# pm2019.net
KiCad netlist of a schematic drawn in EAGLE
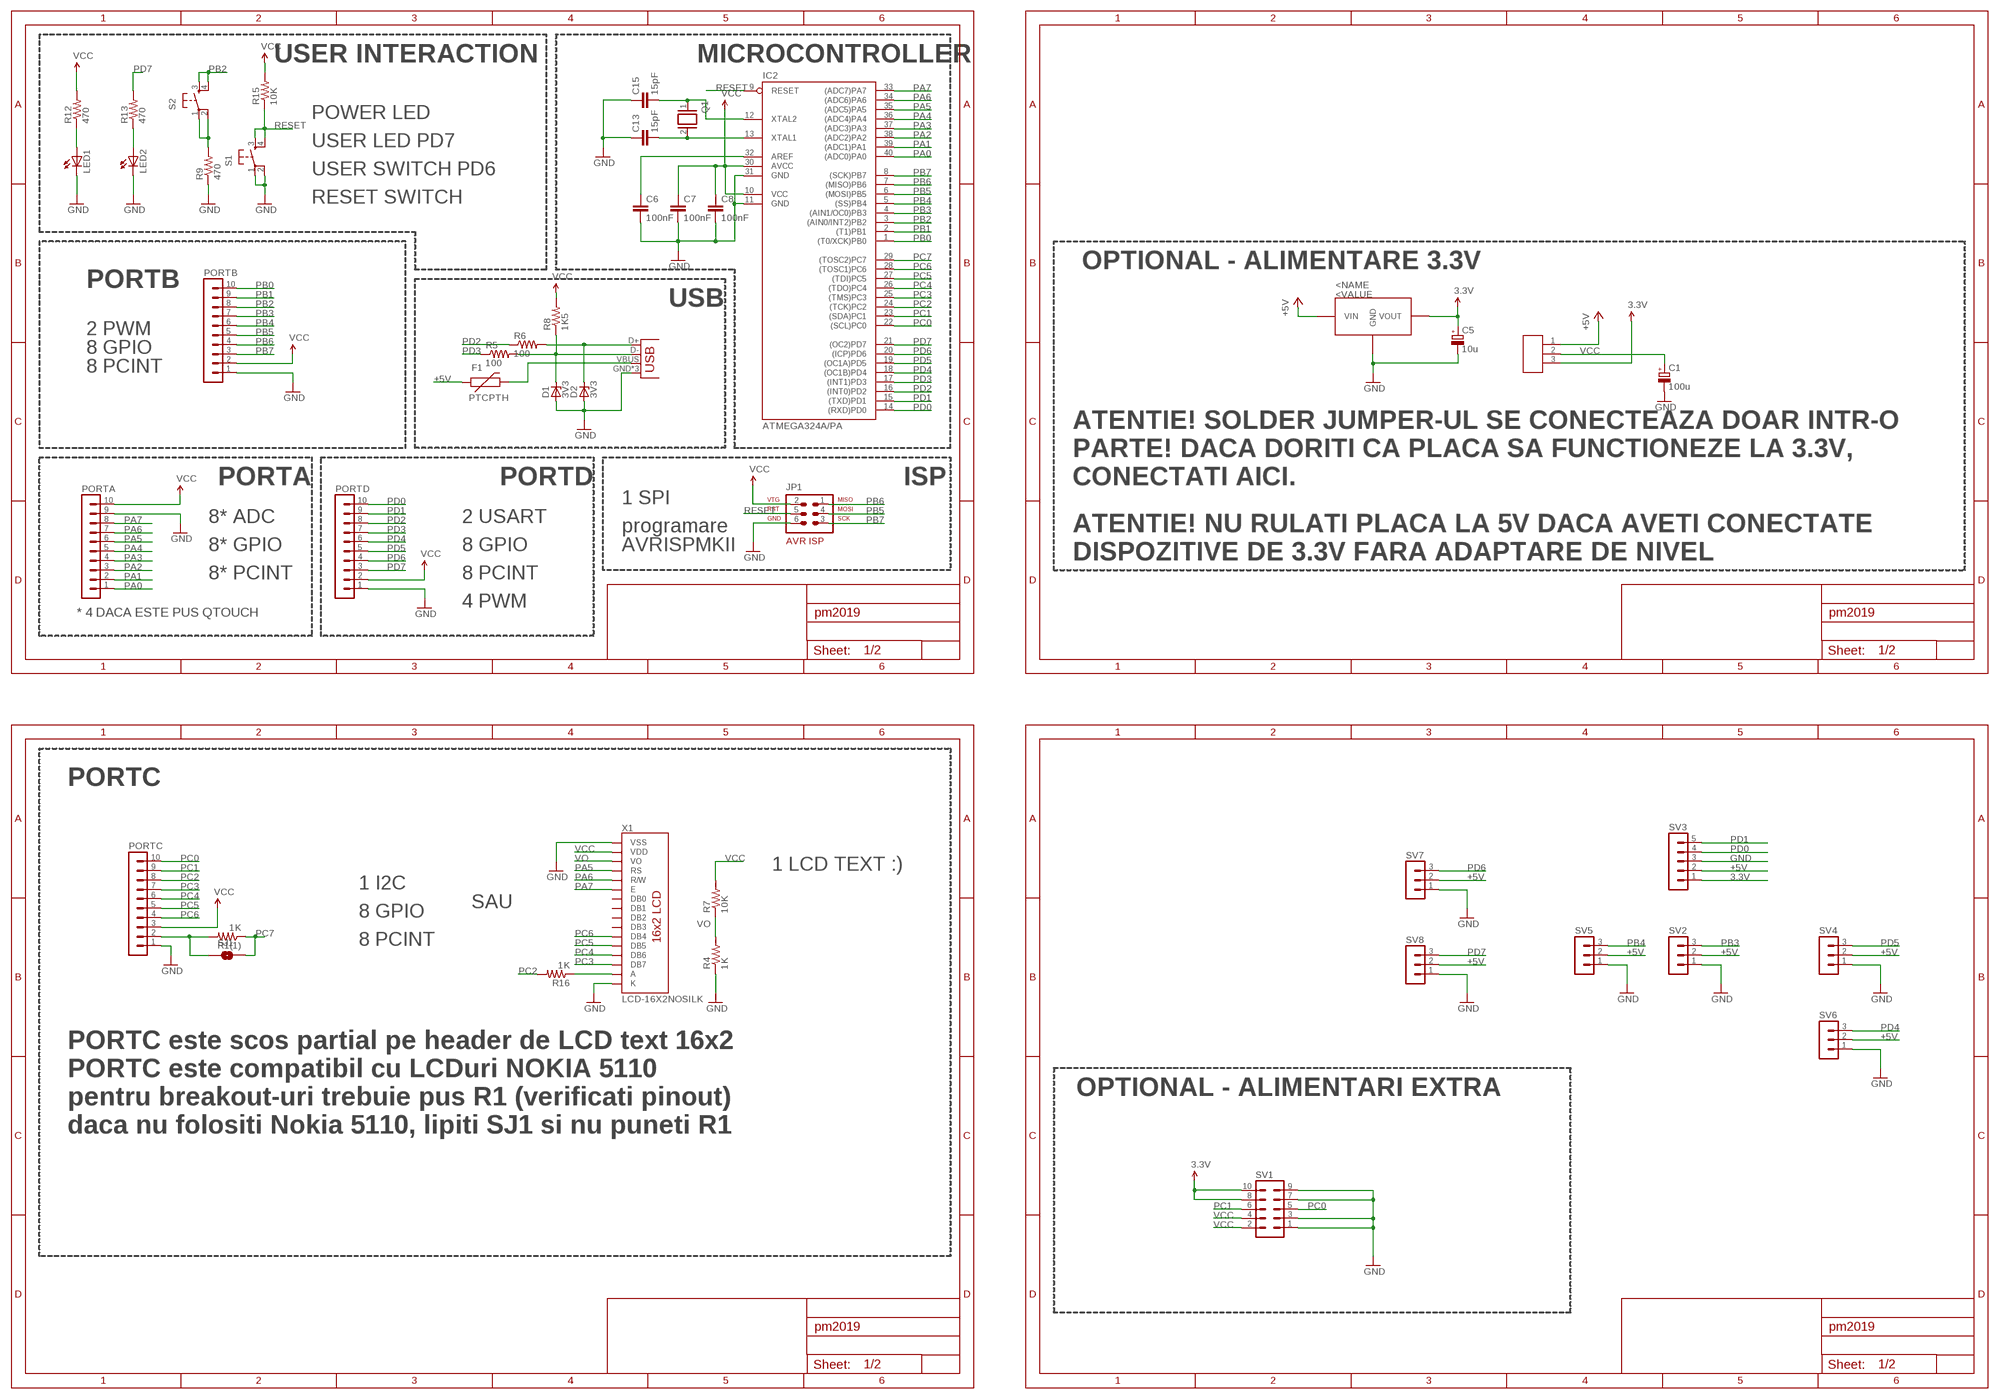
[diagram p0: schematic, sheet 1]
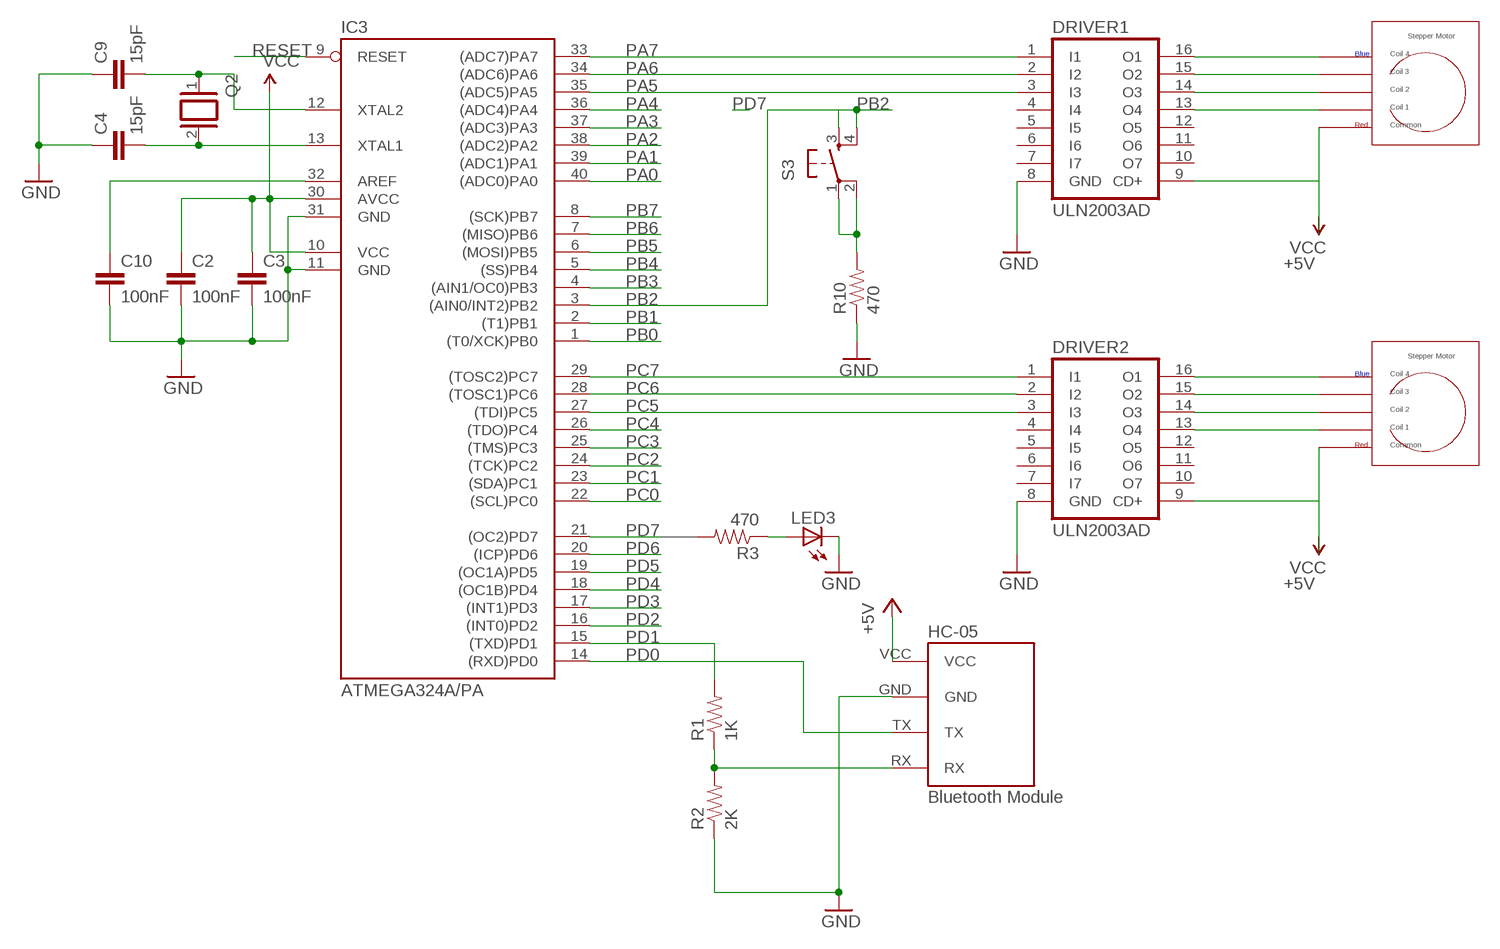
[diagram p1: schematic, sheet 2]

(export (version "E")
  (design (tool "Eeschema 10.0.6"))
  (components
    (comp (ref "C1")
      (value "100u")
      (footprint "eagle-import:E2,5-5")
      (libsource (lib "eagle-import") (part "CPOL-EUE2.5-5"))
    )
    (comp (ref "C5")
      (value "10u")
      (footprint "eagle-import:E2,5-5")
      (libsource (lib "eagle-import") (part "CPOL-EUE2.5-5"))
    )
    (comp (ref "C6")
      (value "100nF")
      (footprint "eagle-import:C025-025X050")
      (libsource (lib "eagle-import") (part "C-EUC_PM"))
    )
    (comp (ref "C7")
      (value "100nF")
      (footprint "eagle-import:C025-025X050")
      (libsource (lib "eagle-import") (part "C-EUC_PM"))
    )
    (comp (ref "C8")
      (value "100nF")
      (footprint "eagle-import:C025-025X050")
      (libsource (lib "eagle-import") (part "C-EUC_PM"))
    )
    (comp (ref "C13")
      (value "15pF")
      (footprint "eagle-import:C025-025X050")
      (libsource (lib "eagle-import") (part "C-EUC_PM"))
    )
    (comp (ref "C15")
      (value "15pF")
      (footprint "eagle-import:C025-025X050")
      (libsource (lib "eagle-import") (part "C-EUC_PM"))
    )
    (comp (ref "D1")
      (value "3V3")
      (footprint "eagle-import:DO34Z7")
      (libsource (lib "eagle-import") (part "ZENER-DIODEDO34-7"))
    )
    (comp (ref "D2")
      (value "3V3")
      (footprint "eagle-import:DO34Z7")
      (libsource (lib "eagle-import") (part "ZENER-DIODEDO34-7"))
    )
    (comp (ref "F1")
      (value "PTCPTH")
      (footprint "eagle-import:PTC")
      (libsource (lib "eagle-import") (part "PTCPTH"))
    )
    (comp (ref "IC1")
      (value "LE33")
      (footprint "eagle-import:TO92")
      (libsource (lib "eagle-import") (part "LE33"))
    )
    (comp (ref "IC2")
      (value "ATMEGA324A/PA")
      (footprint "eagle-import:DIL40")
      (fields (field (name "MPN") "ATMEGA16-16PU"))
      (libsource (lib "eagle-import") (part "MEGA16-P"))
    )
    (comp (ref "J2")
      (value "USBPTH")
      (footprint "eagle-import:USB-B-PTH")
      (libsource (lib "eagle-import") (part "USBPTH"))
    )
    (comp (ref "JP1")
      (value "AVR-ISP-6")
      (footprint "eagle-import:AVR-ISP-6")
      (libsource (lib "eagle-import") (part "AVR-ISP-6"))
    )
    (comp (ref "JP2")
      (value "SJUMPER")
      (footprint "eagle-import:SJUMPER_PACK")
      (libsource (lib "eagle-import") (part "SJUMPER"))
    )
    (comp (ref "LED1")
      (value "LED5MM")
      (footprint "eagle-import:LED5MM")
      (libsource (lib "eagle-import") (part "LED5MM"))
    )
    (comp (ref "LED2")
      (value "LED5MM")
      (footprint "eagle-import:LED5MM")
      (libsource (lib "eagle-import") (part "LED5MM"))
    )
    (comp (ref "PORTA")
      (value "MA10-1")
      (footprint "eagle-import:MA10-1")
      (libsource (lib "eagle-import") (part "MA10-1"))
    )
    (comp (ref "PORTB")
      (value "MA10-1")
      (footprint "eagle-import:MA10-1")
      (libsource (lib "eagle-import") (part "MA10-1"))
    )
    (comp (ref "PORTC")
      (value "MA10-1")
      (footprint "eagle-import:MA10-1")
      (libsource (lib "eagle-import") (part "MA10-1"))
    )
    (comp (ref "PORTD")
      (value "MA10-1")
      (footprint "eagle-import:MA10-1")
      (libsource (lib "eagle-import") (part "MA10-1"))
    )
    (comp (ref "Q1")
      (value "XTAL/S")
      (footprint "eagle-import:QS")
      (libsource (lib "eagle-import") (part "XTAL/S"))
    )
    (comp (ref "R1(1)")
      (value "1K")
      (footprint "eagle-import:AXIAL-0.3")
      (libsource (lib "eagle-import") (part "RESISTORAXIAL-0.3"))
    )
    (comp (ref "R4")
      (value "1K")
      (footprint "eagle-import:AXIAL-0.3")
      (libsource (lib "eagle-import") (part "RESISTORAXIAL-0.3"))
    )
    (comp (ref "R5")
      (value "100")
      (footprint "eagle-import:AXIAL-0.3")
      (libsource (lib "eagle-import") (part "RESISTORAXIAL-0.3"))
    )
    (comp (ref "R6")
      (value "100")
      (footprint "eagle-import:AXIAL-0.3")
      (libsource (lib "eagle-import") (part "RESISTORAXIAL-0.3"))
    )
    (comp (ref "R7")
      (value "10K")
      (footprint "eagle-import:AXIAL-0.3")
      (libsource (lib "eagle-import") (part "RESISTORAXIAL-0.3"))
    )
    (comp (ref "R8")
      (value "1K5")
      (footprint "eagle-import:AXIAL-0.3")
      (libsource (lib "eagle-import") (part "RESISTORAXIAL-0.3"))
    )
    (comp (ref "R9")
      (value "470")
      (footprint "eagle-import:AXIAL-0.3")
      (libsource (lib "eagle-import") (part "RESISTORAXIAL-0.3"))
    )
    (comp (ref "R12")
      (value "470")
      (footprint "eagle-import:AXIAL-0.3")
      (libsource (lib "eagle-import") (part "RESISTORAXIAL-0.3"))
    )
    (comp (ref "R13")
      (value "470")
      (footprint "eagle-import:AXIAL-0.3")
      (libsource (lib "eagle-import") (part "RESISTORAXIAL-0.3"))
    )
    (comp (ref "R15")
      (value "10K")
      (footprint "eagle-import:AXIAL-0.3")
      (libsource (lib "eagle-import") (part "RESISTORAXIAL-0.3"))
    )
    (comp (ref "R16")
      (value "1K")
      (footprint "eagle-import:AXIAL-0.3")
      (libsource (lib "eagle-import") (part "RESISTORAXIAL-0.3"))
    )
    (comp (ref "S1")
      (value "TAC_SWITCHPTH")
      (footprint "eagle-import:TACTILE-PTH")
      (libsource (lib "eagle-import") (part "TAC_SWITCHPTH"))
    )
    (comp (ref "S2")
      (value "TAC_SWITCHPTH")
      (footprint "eagle-import:TACTILE-PTH")
      (libsource (lib "eagle-import") (part "TAC_SWITCHPTH"))
    )
    (comp (ref "SJ1")
      (value "SOLDERJUMPERNC")
      (footprint "eagle-import:SJ-NC")
      (libsource (lib "eagle-import") (part "SOLDERJUMPERNC"))
    )
    (comp (ref "SV1")
      (value "MA05-2")
      (footprint "eagle-import:MA05-2")
      (libsource (lib "eagle-import") (part "MA05-2"))
    )
    (comp (ref "SV2")
      (value "MA03-1")
      (footprint "eagle-import:MA03-1")
      (libsource (lib "eagle-import") (part "MA03-1"))
    )
    (comp (ref "SV3")
      (value "MA05-1")
      (footprint "eagle-import:MA05-1")
      (libsource (lib "eagle-import") (part "MA05-1"))
    )
    (comp (ref "SV4")
      (value "MA03-1")
      (footprint "eagle-import:MA03-1")
      (libsource (lib "eagle-import") (part "MA03-1"))
    )
    (comp (ref "SV5")
      (value "MA03-1")
      (footprint "eagle-import:MA03-1")
      (libsource (lib "eagle-import") (part "MA03-1"))
    )
    (comp (ref "SV6")
      (value "MA03-1")
      (footprint "eagle-import:MA03-1")
      (libsource (lib "eagle-import") (part "MA03-1"))
    )
    (comp (ref "SV7")
      (value "MA03-1")
      (footprint "eagle-import:MA03-1")
      (libsource (lib "eagle-import") (part "MA03-1"))
    )
    (comp (ref "SV8")
      (value "MA03-1")
      (footprint "eagle-import:MA03-1")
      (libsource (lib "eagle-import") (part "MA03-1"))
    )
    (comp (ref "X1")
      (value "LCD-16X2NOSILK")
      (footprint "eagle-import:LCD-16X2_NOSILK")
      (libsource (lib "eagle-import") (part "LCD-16X2NOSILK"))
    )
    (comp (ref "C2")
      (value "100nF")
      (footprint "eagle-import:C025-025X050")
      (libsource (lib "eagle-import") (part "C-EUC_PM"))
    )
    (comp (ref "C3")
      (value "100nF")
      (footprint "eagle-import:C025-025X050")
      (libsource (lib "eagle-import") (part "C-EUC_PM"))
    )
    (comp (ref "C4")
      (value "15pF")
      (footprint "eagle-import:C025-025X050")
      (libsource (lib "eagle-import") (part "C-EUC_PM"))
    )
    (comp (ref "C9")
      (value "15pF")
      (footprint "eagle-import:C025-025X050")
      (libsource (lib "eagle-import") (part "C-EUC_PM"))
    )
    (comp (ref "C10")
      (value "100nF")
      (footprint "eagle-import:C025-025X050")
      (libsource (lib "eagle-import") (part "C-EUC_PM"))
    )
    (comp (ref "DRIVER1")
      (value "ULN2003AD")
      (footprint "eagle-import:SO16")
      (libsource (lib "eagle-import") (part "ULN2003AD"))
    )
    (comp (ref "DRIVER2")
      (value "ULN2003AD")
      (footprint "eagle-import:SO16")
      (libsource (lib "eagle-import") (part "ULN2003AD"))
    )
    (comp (ref "HC-05")
      (value "Bluetooth Module")
      (footprint "eagle-import:BT_BOARD_FOOTPRINT")
      (libsource (lib "eagle-import") (part "BLUETOOTH_BOARD"))
    )
    (comp (ref "IC3")
      (value "ATMEGA324A/PA")
      (footprint "eagle-import:DIL40")
      (fields (field (name "MPN") "ATMEGA16-16PU"))
      (libsource (lib "eagle-import") (part "MEGA16-P"))
    )
    (comp (ref "LED3")
      (value "LED5MM")
      (footprint "eagle-import:LED5MM")
      (libsource (lib "eagle-import") (part "LED5MM"))
    )
    (comp (ref "Q2")
      (value "XTAL/S")
      (footprint "eagle-import:QS")
      (libsource (lib "eagle-import") (part "XTAL/S"))
    )
    (comp (ref "R1")
      (value "1K")
      (footprint "eagle-import:AXIAL-0.3")
      (libsource (lib "eagle-import") (part "RESISTORAXIAL-0.3"))
    )
    (comp (ref "R2")
      (value "2K")
      (footprint "eagle-import:AXIAL-0.3")
      (libsource (lib "eagle-import") (part "RESISTORAXIAL-0.3"))
    )
    (comp (ref "R3")
      (value "470")
      (footprint "eagle-import:AXIAL-0.3")
      (libsource (lib "eagle-import") (part "RESISTORAXIAL-0.3"))
    )
    (comp (ref "R10")
      (value "470")
      (footprint "eagle-import:AXIAL-0.3")
      (libsource (lib "eagle-import") (part "RESISTORAXIAL-0.3"))
    )
    (comp (ref "S3")
      (value "TAC_SWITCHPTH")
      (footprint "eagle-import:TACTILE-PTH")
      (libsource (lib "eagle-import") (part "TAC_SWITCHPTH"))
    )
  )
  (nets
    (net (code "1") (name "+5V") (class "Default")
      (node (ref "F1") (pin "P$1") (pinfunction "1_P$1") (pintype "bidirectional"))
      (node (ref "HC-05") (pin "VCC") (pinfunction "VCC_VCC") (pintype "bidirectional"))
      (node (ref "IC1") (pin "3") (pinfunction "VIN_3") (pintype "bidirectional"))
      (node (ref "JP2") (pin "1") (pinfunction "P$1_1") (pintype "bidirectional"))
      (node (ref "SV2") (pin "2") (pinfunction "2_2") (pintype "passive"))
      (node (ref "SV3") (pin "2") (pinfunction "2_2") (pintype "passive"))
      (node (ref "SV4") (pin "2") (pinfunction "2_2") (pintype "passive"))
      (node (ref "SV5") (pin "2") (pinfunction "2_2") (pintype "passive"))
      (node (ref "SV6") (pin "2") (pinfunction "2_2") (pintype "passive"))
      (node (ref "SV7") (pin "2") (pinfunction "2_2") (pintype "passive"))
      (node (ref "SV8") (pin "2") (pinfunction "2_2") (pintype "passive"))
    )
    (net (code "2") (name "3.3V") (class "Default")
      (node (ref "C5") (pin "+") (pinfunction "+_+") (pintype "passive"))
      (node (ref "IC1") (pin "1") (pinfunction "VOUT_1") (pintype "bidirectional"))
      (node (ref "JP2") (pin "3") (pinfunction "P$3_3") (pintype "bidirectional"))
      (node (ref "SV1") (pin "10") (pinfunction "10_10") (pintype "passive"))
      (node (ref "SV1") (pin "8") (pinfunction "8_8") (pintype "passive"))
      (node (ref "SV3") (pin "1") (pinfunction "1_1") (pintype "passive"))
    )
    (net (code "3") (name "GND") (class "Default")
      (node (ref "C1") (pin "-") (pinfunction "-_-") (pintype "passive"))
      (node (ref "C10") (pin "2") (pinfunction "2_2") (pintype "passive"))
      (node (ref "C13") (pin "1") (pinfunction "1_1") (pintype "passive"))
      (node (ref "C15") (pin "1") (pinfunction "1_1") (pintype "passive"))
      (node (ref "C2") (pin "2") (pinfunction "2_2") (pintype "passive"))
      (node (ref "C3") (pin "2") (pinfunction "2_2") (pintype "passive"))
      (node (ref "C4") (pin "1") (pinfunction "1_1") (pintype "passive"))
      (node (ref "C5") (pin "-") (pinfunction "-_-") (pintype "passive"))
      (node (ref "C6") (pin "2") (pinfunction "2_2") (pintype "passive"))
      (node (ref "C7") (pin "2") (pinfunction "2_2") (pintype "passive"))
      (node (ref "C8") (pin "2") (pinfunction "2_2") (pintype "passive"))
      (node (ref "C9") (pin "1") (pinfunction "1_1") (pintype "passive"))
      (node (ref "D1") (pin "A") (pinfunction "A_A") (pintype "passive"))
      (node (ref "D2") (pin "A") (pinfunction "A_A") (pintype "passive"))
      (node (ref "DRIVER1") (pin "8") (pinfunction "GND_8") (pintype "power_in"))
      (node (ref "DRIVER2") (pin "8") (pinfunction "GND_8") (pintype "power_in"))
      (node (ref "HC-05") (pin "GND") (pinfunction "GND_GND") (pintype "bidirectional"))
      (node (ref "IC1") (pin "2") (pinfunction "GND_2") (pintype "bidirectional"))
      (node (ref "IC2") (pin "11") (pinfunction "GND_11") (pintype "power_in"))
      (node (ref "IC2") (pin "31") (pinfunction "GND_31") (pintype "power_in"))
      (node (ref "IC3") (pin "11") (pinfunction "GND_11") (pintype "power_in"))
      (node (ref "IC3") (pin "31") (pinfunction "GND_31") (pintype "power_in"))
      (node (ref "J2") (pin "GND") (pinfunction "GND_GND") (pintype "bidirectional"))
      (node (ref "J2") (pin "P$1") (pinfunction "GND_P$1") (pintype "bidirectional"))
      (node (ref "J2") (pin "P$2") (pinfunction "GND_P$2") (pintype "bidirectional"))
      (node (ref "JP1") (pin "6") (pinfunction "6_6") (pintype "passive"))
      (node (ref "LED1") (pin "K") (pinfunction "C_K") (pintype "passive"))
      (node (ref "LED2") (pin "K") (pinfunction "C_K") (pintype "passive"))
      (node (ref "LED3") (pin "K") (pinfunction "C_K") (pintype "passive"))
      (node (ref "PORTA") (pin "9") (pinfunction "9_9") (pintype "passive"))
      (node (ref "PORTB") (pin "1") (pinfunction "1_1") (pintype "passive"))
      (node (ref "PORTC") (pin "1") (pinfunction "1_1") (pintype "passive"))
      (node (ref "PORTD") (pin "1") (pinfunction "1_1") (pintype "passive"))
      (node (ref "R10") (pin "P$1") (pinfunction "1_P$1") (pintype "passive"))
      (node (ref "R2") (pin "P$1") (pinfunction "1_P$1") (pintype "passive"))
      (node (ref "R4") (pin "P$1") (pinfunction "1_P$1") (pintype "passive"))
      (node (ref "R9") (pin "P$1") (pinfunction "1_P$1") (pintype "passive"))
      (node (ref "S1") (pin "1") (pinfunction "1_1") (pintype "passive"))
      (node (ref "S1") (pin "2") (pinfunction "2_2") (pintype "passive"))
      (node (ref "SV1") (pin "1") (pinfunction "1_1") (pintype "passive"))
      (node (ref "SV1") (pin "3") (pinfunction "3_3") (pintype "passive"))
      (node (ref "SV1") (pin "7") (pinfunction "7_7") (pintype "passive"))
      (node (ref "SV1") (pin "9") (pinfunction "9_9") (pintype "passive"))
      (node (ref "SV2") (pin "1") (pinfunction "1_1") (pintype "passive"))
      (node (ref "SV3") (pin "3") (pinfunction "3_3") (pintype "passive"))
      (node (ref "SV4") (pin "1") (pinfunction "1_1") (pintype "passive"))
      (node (ref "SV5") (pin "1") (pinfunction "1_1") (pintype "passive"))
      (node (ref "SV6") (pin "1") (pinfunction "1_1") (pintype "passive"))
      (node (ref "SV7") (pin "1") (pinfunction "1_1") (pintype "passive"))
      (node (ref "SV8") (pin "1") (pinfunction "1_1") (pintype "passive"))
      (node (ref "X1") (pin "1") (pinfunction "VSS_1") (pintype "power_in"))
      (node (ref "X1") (pin "16") (pinfunction "K_16") (pintype "power_in"))
    )
    (net (code "4") (name "Net-(F1-2)") (class "Default")
      (node (ref "F1") (pin "P$2") (pinfunction "2_P$2") (pintype "bidirectional"))
      (node (ref "J2") (pin "VBUS") (pinfunction "VBUS_VBUS") (pintype "bidirectional"))
    )
    (net (code "5") (name "Net-(IC2-AREF)") (class "Default")
      (node (ref "C6") (pin "1") (pinfunction "1_1") (pintype "passive"))
      (node (ref "IC2") (pin "32") (pinfunction "AREF_32") (pintype "passive"))
    )
    (net (code "6") (name "Net-(IC2-XTAL1)") (class "Default")
      (node (ref "C13") (pin "2") (pinfunction "2_2") (pintype "passive"))
      (node (ref "IC2") (pin "13") (pinfunction "XTAL1_13") (pintype "bidirectional"))
      (node (ref "Q1") (pin "2") (pinfunction "2_2") (pintype "passive"))
    )
    (net (code "7") (name "Net-(IC2-XTAL2)") (class "Default")
      (node (ref "C15") (pin "2") (pinfunction "2_2") (pintype "passive"))
      (node (ref "IC2") (pin "12") (pinfunction "XTAL2_12") (pintype "bidirectional"))
      (node (ref "Q1") (pin "1") (pinfunction "1_1") (pintype "passive"))
    )
    (net (code "8") (name "Net-(IC3-AREF)") (class "Default")
      (node (ref "C10") (pin "1") (pinfunction "1_1") (pintype "passive"))
      (node (ref "IC3") (pin "32") (pinfunction "AREF_32") (pintype "passive"))
    )
    (net (code "9") (name "Net-(IC3-XTAL1)") (class "Default")
      (node (ref "C4") (pin "2") (pinfunction "2_2") (pintype "passive"))
      (node (ref "IC3") (pin "13") (pinfunction "XTAL1_13") (pintype "bidirectional"))
      (node (ref "Q2") (pin "2") (pinfunction "2_2") (pintype "passive"))
    )
    (net (code "10") (name "Net-(IC3-XTAL2)") (class "Default")
      (node (ref "C9") (pin "2") (pinfunction "2_2") (pintype "passive"))
      (node (ref "IC3") (pin "12") (pinfunction "XTAL2_12") (pintype "bidirectional"))
      (node (ref "Q2") (pin "1") (pinfunction "1_1") (pintype "passive"))
    )
    (net (code "11") (name "Net-(R1(1)-2)") (class "Default")
      (node (ref "PORTC") (pin "2") (pinfunction "2_2") (pintype "passive"))
      (node (ref "R1(1)") (pin "P$2") (pinfunction "2_P$2") (pintype "passive"))
      (node (ref "SJ1") (pin "1") (pinfunction "1_1") (pintype "passive"))
    )
    (net (code "12") (name "Net-(R1-1)") (class "Default")
      (node (ref "HC-05") (pin "RX") (pinfunction "RX_RX") (pintype "bidirectional"))
      (node (ref "R1") (pin "P$1") (pinfunction "1_P$1") (pintype "passive"))
      (node (ref "R2") (pin "P$2") (pinfunction "2_P$2") (pintype "passive"))
    )
    (net (code "13") (name "Net-(R3-1)") (class "Default")
      (node (ref "LED3") (pin "A") (pinfunction "A_A") (pintype "passive"))
      (node (ref "R3") (pin "P$1") (pinfunction "1_P$1") (pintype "passive"))
    )
    (net (code "14") (name "Net-(R5-2)") (class "Default")
      (node (ref "D1") (pin "C") (pinfunction "C_C") (pintype "passive"))
      (node (ref "J2") (pin "D-") (pinfunction "D-_D-") (pintype "bidirectional"))
      (node (ref "R5") (pin "P$2") (pinfunction "2_P$2") (pintype "passive"))
      (node (ref "R8") (pin "P$1") (pinfunction "1_P$1") (pintype "passive"))
    )
    (net (code "15") (name "Net-(R6-2)") (class "Default")
      (node (ref "D2") (pin "C") (pinfunction "C_C") (pintype "passive"))
      (node (ref "J2") (pin "D+") (pinfunction "D+_D+") (pintype "bidirectional"))
      (node (ref "R6") (pin "P$2") (pinfunction "2_P$2") (pintype "passive"))
    )
    (net (code "16") (name "Net-(R9-2)") (class "Default")
      (node (ref "R9") (pin "P$2") (pinfunction "2_P$2") (pintype "passive"))
      (node (ref "S2") (pin "1") (pinfunction "1_1") (pintype "passive"))
      (node (ref "S2") (pin "2") (pinfunction "2_2") (pintype "passive"))
    )
    (net (code "17") (name "Net-(R10-2)") (class "Default")
      (node (ref "R10") (pin "P$2") (pinfunction "2_P$2") (pintype "passive"))
      (node (ref "S3") (pin "1") (pinfunction "1_1") (pintype "passive"))
      (node (ref "S3") (pin "2") (pinfunction "2_2") (pintype "passive"))
    )
    (net (code "18") (name "Net-(R12-1)") (class "Default")
      (node (ref "LED1") (pin "A") (pinfunction "A_A") (pintype "passive"))
      (node (ref "R12") (pin "P$1") (pinfunction "1_P$1") (pintype "passive"))
    )
    (net (code "19") (name "Net-(R13-1)") (class "Default")
      (node (ref "LED2") (pin "A") (pinfunction "A_A") (pintype "passive"))
      (node (ref "R13") (pin "P$1") (pinfunction "1_P$1") (pintype "passive"))
    )
    (net (code "20") (name "Net-(R16-1)") (class "Default")
      (node (ref "R16") (pin "P$1") (pinfunction "1_P$1") (pintype "passive"))
      (node (ref "X1") (pin "15") (pinfunction "A_15") (pintype "power_in"))
    )
    (net (code "21") (name "PA0") (class "Default")
      (node (ref "IC2") (pin "40") (pinfunction "(ADC0)PA0_40") (pintype "bidirectional"))
      (node (ref "IC3") (pin "40") (pinfunction "(ADC0)PA0_40") (pintype "bidirectional"))
      (node (ref "PORTA") (pin "1") (pinfunction "1_1") (pintype "passive"))
    )
    (net (code "22") (name "PA1") (class "Default")
      (node (ref "IC2") (pin "39") (pinfunction "(ADC1)PA1_39") (pintype "bidirectional"))
      (node (ref "IC3") (pin "39") (pinfunction "(ADC1)PA1_39") (pintype "bidirectional"))
      (node (ref "PORTA") (pin "2") (pinfunction "2_2") (pintype "passive"))
    )
    (net (code "23") (name "PA2") (class "Default")
      (node (ref "IC2") (pin "38") (pinfunction "(ADC2)PA2_38") (pintype "bidirectional"))
      (node (ref "IC3") (pin "38") (pinfunction "(ADC2)PA2_38") (pintype "bidirectional"))
      (node (ref "PORTA") (pin "3") (pinfunction "3_3") (pintype "passive"))
    )
    (net (code "24") (name "PA3") (class "Default")
      (node (ref "IC2") (pin "37") (pinfunction "(ADC3)PA3_37") (pintype "bidirectional"))
      (node (ref "IC3") (pin "37") (pinfunction "(ADC3)PA3_37") (pintype "bidirectional"))
      (node (ref "PORTA") (pin "4") (pinfunction "4_4") (pintype "passive"))
    )
    (net (code "25") (name "PA4") (class "Default")
      (node (ref "IC2") (pin "36") (pinfunction "(ADC4)PA4_36") (pintype "bidirectional"))
      (node (ref "IC3") (pin "36") (pinfunction "(ADC4)PA4_36") (pintype "bidirectional"))
      (node (ref "PORTA") (pin "5") (pinfunction "5_5") (pintype "passive"))
    )
    (net (code "26") (name "PA5") (class "Default")
      (node (ref "DRIVER1") (pin "3") (pinfunction "I3_3") (pintype "input"))
      (node (ref "IC2") (pin "35") (pinfunction "(ADC5)PA5_35") (pintype "bidirectional"))
      (node (ref "IC3") (pin "35") (pinfunction "(ADC5)PA5_35") (pintype "bidirectional"))
      (node (ref "PORTA") (pin "6") (pinfunction "6_6") (pintype "passive"))
      (node (ref "X1") (pin "4") (pinfunction "RS_4") (pintype "input"))
    )
    (net (code "27") (name "PA6") (class "Default")
      (node (ref "DRIVER1") (pin "2") (pinfunction "I2_2") (pintype "input"))
      (node (ref "IC2") (pin "34") (pinfunction "(ADC6)PA6_34") (pintype "bidirectional"))
      (node (ref "IC3") (pin "34") (pinfunction "(ADC6)PA6_34") (pintype "bidirectional"))
      (node (ref "PORTA") (pin "7") (pinfunction "7_7") (pintype "passive"))
      (node (ref "X1") (pin "5") (pinfunction "R/W_5") (pintype "input"))
    )
    (net (code "28") (name "PA7") (class "Default")
      (node (ref "DRIVER1") (pin "1") (pinfunction "I1_1") (pintype "input"))
      (node (ref "IC2") (pin "33") (pinfunction "(ADC7)PA7_33") (pintype "bidirectional"))
      (node (ref "IC3") (pin "33") (pinfunction "(ADC7)PA7_33") (pintype "bidirectional"))
      (node (ref "PORTA") (pin "8") (pinfunction "8_8") (pintype "passive"))
      (node (ref "X1") (pin "6") (pinfunction "E_6") (pintype "input"))
    )
    (net (code "29") (name "PB0") (class "Default")
      (node (ref "IC2") (pin "1") (pinfunction "(T0/XCK)PB0_1") (pintype "bidirectional"))
      (node (ref "IC3") (pin "1") (pinfunction "(T0/XCK)PB0_1") (pintype "bidirectional"))
      (node (ref "PORTB") (pin "10") (pinfunction "10_10") (pintype "passive"))
    )
    (net (code "30") (name "PB1") (class "Default")
      (node (ref "IC2") (pin "2") (pinfunction "(T1)PB1_2") (pintype "bidirectional"))
      (node (ref "IC3") (pin "2") (pinfunction "(T1)PB1_2") (pintype "bidirectional"))
      (node (ref "PORTB") (pin "9") (pinfunction "9_9") (pintype "passive"))
    )
    (net (code "31") (name "PB2") (class "Default")
      (node (ref "IC2") (pin "3") (pinfunction "(AIN0/INT2)PB2_3") (pintype "bidirectional"))
      (node (ref "IC3") (pin "3") (pinfunction "(AIN0/INT2)PB2_3") (pintype "bidirectional"))
      (node (ref "PORTB") (pin "8") (pinfunction "8_8") (pintype "passive"))
      (node (ref "S2") (pin "3") (pinfunction "3_3") (pintype "passive"))
      (node (ref "S2") (pin "4") (pinfunction "4_4") (pintype "passive"))
      (node (ref "S3") (pin "3") (pinfunction "3_3") (pintype "passive"))
      (node (ref "S3") (pin "4") (pinfunction "4_4") (pintype "passive"))
    )
    (net (code "32") (name "PB3") (class "Default")
      (node (ref "IC2") (pin "4") (pinfunction "(AIN1/OC0)PB3_4") (pintype "bidirectional"))
      (node (ref "IC3") (pin "4") (pinfunction "(AIN1/OC0)PB3_4") (pintype "bidirectional"))
      (node (ref "PORTB") (pin "7") (pinfunction "7_7") (pintype "passive"))
      (node (ref "SV2") (pin "3") (pinfunction "3_3") (pintype "passive"))
    )
    (net (code "33") (name "PB4") (class "Default")
      (node (ref "IC2") (pin "5") (pinfunction "(SS)PB4_5") (pintype "bidirectional"))
      (node (ref "IC3") (pin "5") (pinfunction "(SS)PB4_5") (pintype "bidirectional"))
      (node (ref "PORTB") (pin "6") (pinfunction "6_6") (pintype "passive"))
      (node (ref "SV5") (pin "3") (pinfunction "3_3") (pintype "passive"))
    )
    (net (code "34") (name "PB5") (class "Default")
      (node (ref "IC2") (pin "6") (pinfunction "(MOSI)PB5_6") (pintype "bidirectional"))
      (node (ref "IC3") (pin "6") (pinfunction "(MOSI)PB5_6") (pintype "bidirectional"))
      (node (ref "JP1") (pin "4") (pinfunction "4_4") (pintype "passive"))
      (node (ref "PORTB") (pin "5") (pinfunction "5_5") (pintype "passive"))
    )
    (net (code "35") (name "PB6") (class "Default")
      (node (ref "IC2") (pin "7") (pinfunction "(MISO)PB6_7") (pintype "bidirectional"))
      (node (ref "IC3") (pin "7") (pinfunction "(MISO)PB6_7") (pintype "bidirectional"))
      (node (ref "JP1") (pin "1") (pinfunction "1_1") (pintype "passive"))
      (node (ref "PORTB") (pin "4") (pinfunction "4_4") (pintype "passive"))
    )
    (net (code "36") (name "PB7") (class "Default")
      (node (ref "IC2") (pin "8") (pinfunction "(SCK)PB7_8") (pintype "bidirectional"))
      (node (ref "IC3") (pin "8") (pinfunction "(SCK)PB7_8") (pintype "bidirectional"))
      (node (ref "JP1") (pin "3") (pinfunction "3_3") (pintype "passive"))
      (node (ref "PORTB") (pin "3") (pinfunction "3_3") (pintype "passive"))
    )
    (net (code "37") (name "PC0") (class "Default")
      (node (ref "IC2") (pin "22") (pinfunction "(SCL)PC0_22") (pintype "bidirectional"))
      (node (ref "IC3") (pin "22") (pinfunction "(SCL)PC0_22") (pintype "bidirectional"))
      (node (ref "PORTC") (pin "10") (pinfunction "10_10") (pintype "passive"))
      (node (ref "SV1") (pin "5") (pinfunction "5_5") (pintype "passive"))
    )
    (net (code "38") (name "PC1") (class "Default")
      (node (ref "IC2") (pin "23") (pinfunction "(SDA)PC1_23") (pintype "bidirectional"))
      (node (ref "IC3") (pin "23") (pinfunction "(SDA)PC1_23") (pintype "bidirectional"))
      (node (ref "PORTC") (pin "9") (pinfunction "9_9") (pintype "passive"))
      (node (ref "SV1") (pin "6") (pinfunction "6_6") (pintype "passive"))
    )
    (net (code "39") (name "PC2") (class "Default")
      (node (ref "IC2") (pin "24") (pinfunction "(TCK)PC2_24") (pintype "bidirectional"))
      (node (ref "IC3") (pin "24") (pinfunction "(TCK)PC2_24") (pintype "bidirectional"))
      (node (ref "PORTC") (pin "8") (pinfunction "8_8") (pintype "passive"))
      (node (ref "R16") (pin "P$2") (pinfunction "2_P$2") (pintype "passive"))
    )
    (net (code "40") (name "PC3") (class "Default")
      (node (ref "IC2") (pin "25") (pinfunction "(TMS)PC3_25") (pintype "bidirectional"))
      (node (ref "IC3") (pin "25") (pinfunction "(TMS)PC3_25") (pintype "bidirectional"))
      (node (ref "PORTC") (pin "7") (pinfunction "7_7") (pintype "passive"))
      (node (ref "X1") (pin "14") (pinfunction "DB7_14") (pintype "bidirectional"))
    )
    (net (code "41") (name "PC4") (class "Default")
      (node (ref "IC2") (pin "26") (pinfunction "(TDO)PC4_26") (pintype "bidirectional"))
      (node (ref "IC3") (pin "26") (pinfunction "(TDO)PC4_26") (pintype "bidirectional"))
      (node (ref "PORTC") (pin "6") (pinfunction "6_6") (pintype "passive"))
      (node (ref "X1") (pin "13") (pinfunction "DB6_13") (pintype "bidirectional"))
    )
    (net (code "42") (name "PC5") (class "Default")
      (node (ref "DRIVER2") (pin "3") (pinfunction "I3_3") (pintype "input"))
      (node (ref "IC2") (pin "27") (pinfunction "(TDI)PC5_27") (pintype "bidirectional"))
      (node (ref "IC3") (pin "27") (pinfunction "(TDI)PC5_27") (pintype "bidirectional"))
      (node (ref "PORTC") (pin "5") (pinfunction "5_5") (pintype "passive"))
      (node (ref "X1") (pin "12") (pinfunction "DB5_12") (pintype "bidirectional"))
    )
    (net (code "43") (name "PC6") (class "Default")
      (node (ref "DRIVER2") (pin "2") (pinfunction "I2_2") (pintype "input"))
      (node (ref "IC2") (pin "28") (pinfunction "(TOSC1)PC6_28") (pintype "bidirectional"))
      (node (ref "IC3") (pin "28") (pinfunction "(TOSC1)PC6_28") (pintype "bidirectional"))
      (node (ref "PORTC") (pin "4") (pinfunction "4_4") (pintype "passive"))
      (node (ref "X1") (pin "11") (pinfunction "DB4_11") (pintype "bidirectional"))
    )
    (net (code "44") (name "PC7") (class "Default")
      (node (ref "DRIVER2") (pin "1") (pinfunction "I1_1") (pintype "input"))
      (node (ref "IC2") (pin "29") (pinfunction "(TOSC2)PC7_29") (pintype "bidirectional"))
      (node (ref "IC3") (pin "29") (pinfunction "(TOSC2)PC7_29") (pintype "bidirectional"))
      (node (ref "R1(1)") (pin "P$1") (pinfunction "1_P$1") (pintype "passive"))
      (node (ref "SJ1") (pin "2") (pinfunction "2_2") (pintype "passive"))
    )
    (net (code "45") (name "PD0") (class "Default")
      (node (ref "HC-05") (pin "TX") (pinfunction "TX_TX") (pintype "bidirectional"))
      (node (ref "IC2") (pin "14") (pinfunction "(RXD)PD0_14") (pintype "bidirectional"))
      (node (ref "IC3") (pin "14") (pinfunction "(RXD)PD0_14") (pintype "bidirectional"))
      (node (ref "PORTD") (pin "10") (pinfunction "10_10") (pintype "passive"))
      (node (ref "SV3") (pin "4") (pinfunction "4_4") (pintype "passive"))
    )
    (net (code "46") (name "PD1") (class "Default")
      (node (ref "IC2") (pin "15") (pinfunction "(TXD)PD1_15") (pintype "bidirectional"))
      (node (ref "IC3") (pin "15") (pinfunction "(TXD)PD1_15") (pintype "bidirectional"))
      (node (ref "PORTD") (pin "9") (pinfunction "9_9") (pintype "passive"))
      (node (ref "R1") (pin "P$2") (pinfunction "2_P$2") (pintype "passive"))
      (node (ref "SV3") (pin "5") (pinfunction "5_5") (pintype "passive"))
    )
    (net (code "47") (name "PD2") (class "Default")
      (node (ref "IC2") (pin "16") (pinfunction "(INT0)PD2_16") (pintype "bidirectional"))
      (node (ref "IC3") (pin "16") (pinfunction "(INT0)PD2_16") (pintype "bidirectional"))
      (node (ref "PORTD") (pin "8") (pinfunction "8_8") (pintype "passive"))
      (node (ref "R6") (pin "P$1") (pinfunction "1_P$1") (pintype "passive"))
    )
    (net (code "48") (name "PD3") (class "Default")
      (node (ref "IC2") (pin "17") (pinfunction "(INT1)PD3_17") (pintype "bidirectional"))
      (node (ref "IC3") (pin "17") (pinfunction "(INT1)PD3_17") (pintype "bidirectional"))
      (node (ref "PORTD") (pin "7") (pinfunction "7_7") (pintype "passive"))
      (node (ref "R5") (pin "P$1") (pinfunction "1_P$1") (pintype "passive"))
    )
    (net (code "49") (name "PD4") (class "Default")
      (node (ref "IC2") (pin "18") (pinfunction "(OC1B)PD4_18") (pintype "bidirectional"))
      (node (ref "IC3") (pin "18") (pinfunction "(OC1B)PD4_18") (pintype "bidirectional"))
      (node (ref "PORTD") (pin "6") (pinfunction "6_6") (pintype "passive"))
      (node (ref "SV6") (pin "3") (pinfunction "3_3") (pintype "passive"))
    )
    (net (code "50") (name "PD5") (class "Default")
      (node (ref "IC2") (pin "19") (pinfunction "(OC1A)PD5_19") (pintype "bidirectional"))
      (node (ref "IC3") (pin "19") (pinfunction "(OC1A)PD5_19") (pintype "bidirectional"))
      (node (ref "PORTD") (pin "5") (pinfunction "5_5") (pintype "passive"))
      (node (ref "SV4") (pin "3") (pinfunction "3_3") (pintype "passive"))
    )
    (net (code "51") (name "PD6") (class "Default")
      (node (ref "IC2") (pin "20") (pinfunction "(ICP)PD6_20") (pintype "bidirectional"))
      (node (ref "IC3") (pin "20") (pinfunction "(ICP)PD6_20") (pintype "bidirectional"))
      (node (ref "PORTD") (pin "4") (pinfunction "4_4") (pintype "passive"))
      (node (ref "SV7") (pin "3") (pinfunction "3_3") (pintype "passive"))
    )
    (net (code "52") (name "PD7") (class "Default")
      (node (ref "IC2") (pin "21") (pinfunction "(OC2)PD7_21") (pintype "bidirectional"))
      (node (ref "IC3") (pin "21") (pinfunction "(OC2)PD7_21") (pintype "bidirectional"))
      (node (ref "PORTD") (pin "3") (pinfunction "3_3") (pintype "passive"))
      (node (ref "R13") (pin "P$2") (pinfunction "2_P$2") (pintype "passive"))
      (node (ref "SV8") (pin "3") (pinfunction "3_3") (pintype "passive"))
    )
    (net (code "53") (name "RESET") (class "Default")
      (node (ref "IC2") (pin "9") (pinfunction "RESET_9") (pintype "input"))
      (node (ref "IC3") (pin "9") (pinfunction "RESET_9") (pintype "input"))
      (node (ref "JP1") (pin "5") (pinfunction "5_5") (pintype "passive"))
      (node (ref "R15") (pin "P$1") (pinfunction "1_P$1") (pintype "passive"))
      (node (ref "S1") (pin "3") (pinfunction "3_3") (pintype "passive"))
      (node (ref "S1") (pin "4") (pinfunction "4_4") (pintype "passive"))
    )
    (net (code "54") (name "VCC") (class "Default")
      (node (ref "C1") (pin "+") (pinfunction "+_+") (pintype "passive"))
      (node (ref "C2") (pin "1") (pinfunction "1_1") (pintype "passive"))
      (node (ref "C3") (pin "1") (pinfunction "1_1") (pintype "passive"))
      (node (ref "C7") (pin "1") (pinfunction "1_1") (pintype "passive"))
      (node (ref "C8") (pin "1") (pinfunction "1_1") (pintype "passive"))
      (node (ref "DRIVER1") (pin "9") (pinfunction "CD+_9") (pintype "passive"))
      (node (ref "DRIVER2") (pin "9") (pinfunction "CD+_9") (pintype "passive"))
      (node (ref "IC2") (pin "10") (pinfunction "VCC_10") (pintype "power_in"))
      (node (ref "IC2") (pin "30") (pinfunction "AVCC_30") (pintype "power_in"))
      (node (ref "IC3") (pin "10") (pinfunction "VCC_10") (pintype "power_in"))
      (node (ref "IC3") (pin "30") (pinfunction "AVCC_30") (pintype "power_in"))
      (node (ref "JP1") (pin "2") (pinfunction "2_2") (pintype "passive"))
      (node (ref "JP2") (pin "2") (pinfunction "P$2_2") (pintype "bidirectional"))
      (node (ref "PORTA") (pin "10") (pinfunction "10_10") (pintype "passive"))
      (node (ref "PORTB") (pin "2") (pinfunction "2_2") (pintype "passive"))
      (node (ref "PORTC") (pin "3") (pinfunction "3_3") (pintype "passive"))
      (node (ref "PORTD") (pin "2") (pinfunction "2_2") (pintype "passive"))
      (node (ref "R12") (pin "P$2") (pinfunction "2_P$2") (pintype "passive"))
      (node (ref "R15") (pin "P$2") (pinfunction "2_P$2") (pintype "passive"))
      (node (ref "R7") (pin "P$2") (pinfunction "2_P$2") (pintype "passive"))
      (node (ref "R8") (pin "P$2") (pinfunction "2_P$2") (pintype "passive"))
      (node (ref "SV1") (pin "2") (pinfunction "2_2") (pintype "passive"))
      (node (ref "SV1") (pin "4") (pinfunction "4_4") (pintype "passive"))
      (node (ref "X1") (pin "2") (pinfunction "VDD_2") (pintype "power_in"))
    )
    (net (code "55") (name "VO") (class "Default")
      (node (ref "R4") (pin "P$2") (pinfunction "2_P$2") (pintype "passive"))
      (node (ref "R7") (pin "P$1") (pinfunction "1_P$1") (pintype "passive"))
      (node (ref "X1") (pin "3") (pinfunction "VO_3") (pintype "bidirectional"))
    )
    (net (code "56") (name "unconnected-(DRIVER1-I4-Pad4)") (class "Default")
      (node (ref "DRIVER1") (pin "4") (pinfunction "I4_4") (pintype "input"))
    )
    (net (code "57") (name "unconnected-(DRIVER1-I5-Pad5)") (class "Default")
      (node (ref "DRIVER1") (pin "5") (pinfunction "I5_5") (pintype "input"))
    )
    (net (code "58") (name "unconnected-(DRIVER1-I6-Pad6)") (class "Default")
      (node (ref "DRIVER1") (pin "6") (pinfunction "I6_6") (pintype "input"))
    )
    (net (code "59") (name "unconnected-(DRIVER1-I7-Pad7)") (class "Default")
      (node (ref "DRIVER1") (pin "7") (pinfunction "I7_7") (pintype "input"))
    )
    (net (code "60") (name "unconnected-(DRIVER1-O1-Pad16)") (class "Default")
      (node (ref "DRIVER1") (pin "16") (pinfunction "O1_16") (pintype "open_collector"))
    )
    (net (code "61") (name "unconnected-(DRIVER1-O2-Pad15)") (class "Default")
      (node (ref "DRIVER1") (pin "15") (pinfunction "O2_15") (pintype "open_collector"))
    )
    (net (code "62") (name "unconnected-(DRIVER1-O3-Pad14)") (class "Default")
      (node (ref "DRIVER1") (pin "14") (pinfunction "O3_14") (pintype "open_collector"))
    )
    (net (code "63") (name "unconnected-(DRIVER1-O4-Pad13)") (class "Default")
      (node (ref "DRIVER1") (pin "13") (pinfunction "O4_13") (pintype "open_collector"))
    )
    (net (code "64") (name "unconnected-(DRIVER1-O5-Pad12)") (class "Default")
      (node (ref "DRIVER1") (pin "12") (pinfunction "O5_12") (pintype "open_collector"))
    )
    (net (code "65") (name "unconnected-(DRIVER1-O6-Pad11)") (class "Default")
      (node (ref "DRIVER1") (pin "11") (pinfunction "O6_11") (pintype "open_collector"))
    )
    (net (code "66") (name "unconnected-(DRIVER1-O7-Pad10)") (class "Default")
      (node (ref "DRIVER1") (pin "10") (pinfunction "O7_10") (pintype "open_collector"))
    )
    (net (code "67") (name "unconnected-(DRIVER2-I4-Pad4)") (class "Default")
      (node (ref "DRIVER2") (pin "4") (pinfunction "I4_4") (pintype "input"))
    )
    (net (code "68") (name "unconnected-(DRIVER2-I5-Pad5)") (class "Default")
      (node (ref "DRIVER2") (pin "5") (pinfunction "I5_5") (pintype "input"))
    )
    (net (code "69") (name "unconnected-(DRIVER2-I6-Pad6)") (class "Default")
      (node (ref "DRIVER2") (pin "6") (pinfunction "I6_6") (pintype "input"))
    )
    (net (code "70") (name "unconnected-(DRIVER2-I7-Pad7)") (class "Default")
      (node (ref "DRIVER2") (pin "7") (pinfunction "I7_7") (pintype "input"))
    )
    (net (code "71") (name "unconnected-(DRIVER2-O1-Pad16)") (class "Default")
      (node (ref "DRIVER2") (pin "16") (pinfunction "O1_16") (pintype "open_collector"))
    )
    (net (code "72") (name "unconnected-(DRIVER2-O2-Pad15)") (class "Default")
      (node (ref "DRIVER2") (pin "15") (pinfunction "O2_15") (pintype "open_collector"))
    )
    (net (code "73") (name "unconnected-(DRIVER2-O3-Pad14)") (class "Default")
      (node (ref "DRIVER2") (pin "14") (pinfunction "O3_14") (pintype "open_collector"))
    )
    (net (code "74") (name "unconnected-(DRIVER2-O4-Pad13)") (class "Default")
      (node (ref "DRIVER2") (pin "13") (pinfunction "O4_13") (pintype "open_collector"))
    )
    (net (code "75") (name "unconnected-(DRIVER2-O5-Pad12)") (class "Default")
      (node (ref "DRIVER2") (pin "12") (pinfunction "O5_12") (pintype "open_collector"))
    )
    (net (code "76") (name "unconnected-(DRIVER2-O6-Pad11)") (class "Default")
      (node (ref "DRIVER2") (pin "11") (pinfunction "O6_11") (pintype "open_collector"))
    )
    (net (code "77") (name "unconnected-(DRIVER2-O7-Pad10)") (class "Default")
      (node (ref "DRIVER2") (pin "10") (pinfunction "O7_10") (pintype "open_collector"))
    )
    (net (code "78") (name "unconnected-(R3-2-PadP$2)") (class "Default")
      (node (ref "R3") (pin "P$2") (pinfunction "2_P$2") (pintype "passive"))
    )
    (net (code "79") (name "unconnected-(X1-DB0-Pad7)") (class "Default")
      (node (ref "X1") (pin "7") (pinfunction "DB0_7") (pintype "bidirectional"))
    )
    (net (code "80") (name "unconnected-(X1-DB1-Pad8)") (class "Default")
      (node (ref "X1") (pin "8") (pinfunction "DB1_8") (pintype "bidirectional"))
    )
    (net (code "81") (name "unconnected-(X1-DB2-Pad9)") (class "Default")
      (node (ref "X1") (pin "9") (pinfunction "DB2_9") (pintype "bidirectional"))
    )
    (net (code "82") (name "unconnected-(X1-DB3-Pad10)") (class "Default")
      (node (ref "X1") (pin "10") (pinfunction "DB3_10") (pintype "bidirectional"))
    )
  )
)
